# uc3906_New_Version.net
KiCad netlist of a schematic drawn in EAGLE
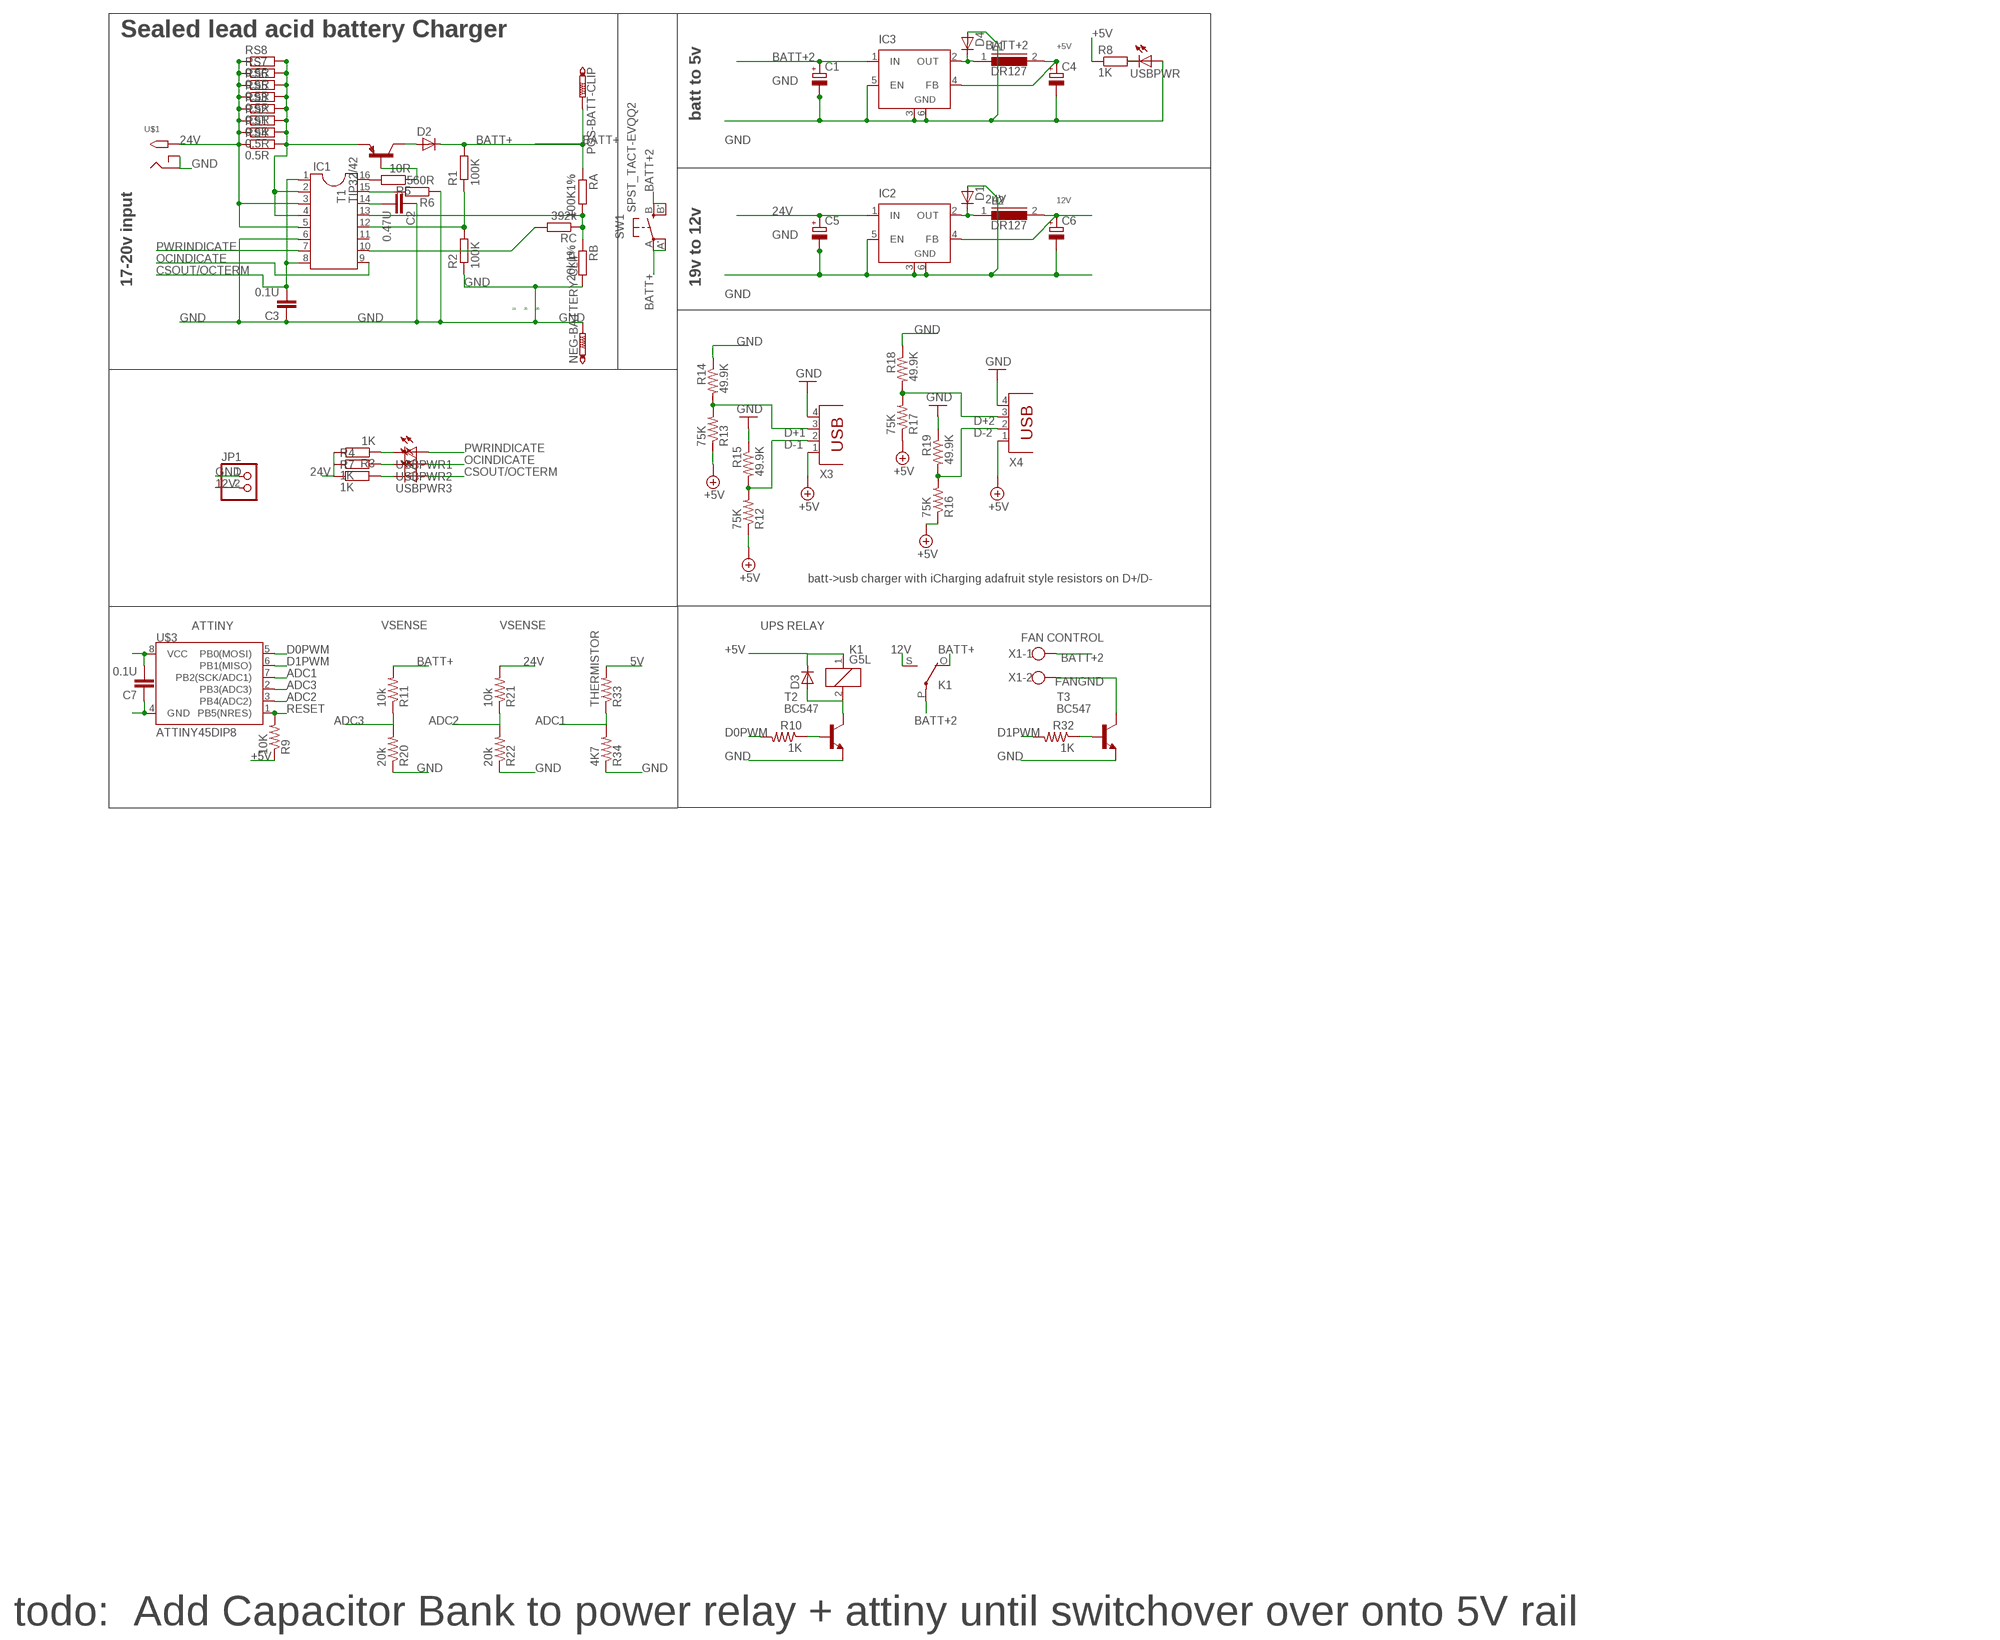
[diagram p0: schematic, sheet 1]

(export (version "E")
  (design (tool "Eeschema 10.0.6"))
  (components
    (comp (ref "C1")
      (value "CPOL-EUE")
      (footprint "eagle-import:PANASONIC_E")
      (libsource (lib "eagle-import") (part "CPOL-EUE"))
    )
    (comp (ref "C2")
      (value "0.47U")
      (footprint "eagle-import:C1206")
      (libsource (lib "eagle-import") (part "C-EUC1206"))
    )
    (comp (ref "C3")
      (value "0.1U")
      (footprint "eagle-import:C1206")
      (libsource (lib "eagle-import") (part "C-EUC1206"))
    )
    (comp (ref "C4")
      (value "CPOL-EUE")
      (footprint "eagle-import:PANASONIC_E")
      (libsource (lib "eagle-import") (part "CPOL-EUE"))
    )
    (comp (ref "C5")
      (value "CPOL-EUE")
      (footprint "eagle-import:PANASONIC_E")
      (libsource (lib "eagle-import") (part "CPOL-EUE"))
    )
    (comp (ref "C6")
      (value "CPOL-EUE")
      (footprint "eagle-import:PANASONIC_E")
      (libsource (lib "eagle-import") (part "CPOL-EUE"))
    )
    (comp (ref "C7")
      (value "0.1U")
      (footprint "eagle-import:C1206")
      (libsource (lib "eagle-import") (part "C-EUC1206"))
    )
    (comp (ref "D1")
      (value "D-SOD-87")
      (footprint "eagle-import:SOD87")
      (libsource (lib "eagle-import") (part "D-SOD-87"))
    )
    (comp (ref "D2")
      (value "D-MLL-41")
      (footprint "eagle-import:MELF-MLL41")
      (libsource (lib "eagle-import") (part "D-MLL-41"))
    )
    (comp (ref "D3")
      (value "D-MLL-41")
      (footprint "eagle-import:MELF-MLL41")
      (libsource (lib "eagle-import") (part "D-MLL-41"))
    )
    (comp (ref "D4")
      (value "D-SOD-87")
      (footprint "eagle-import:SOD87")
      (libsource (lib "eagle-import") (part "D-SOD-87"))
    )
    (comp (ref "IC1")
      (value "DIL16")
      (footprint "eagle-import:DIL16")
      (libsource (lib "eagle-import") (part "DIL16"))
    )
    (comp (ref "IC2")
      (value "LM2596S")
      (footprint "eagle-import:TO263-5")
      (libsource (lib "eagle-import") (part "LM2596S"))
    )
    (comp (ref "IC3")
      (value "LM2596S")
      (footprint "eagle-import:TO263-5")
      (libsource (lib "eagle-import") (part "LM2596S"))
    )
    (comp (ref "JP1")
      (value "PINHD-1X2")
      (footprint "eagle-import:1X02")
      (libsource (lib "eagle-import") (part "PINHD-1X2"))
    )
    (comp (ref "K1")
      (value "G5L")
      (footprint "eagle-import:G5LE")
      (libsource (lib "eagle-import") (part "G5L"))
    )
    (comp (ref "L1")
      (value "DR127")
      (footprint "eagle-import:DR127")
      (libsource (lib "eagle-import") (part "DR127"))
    )
    (comp (ref "L2")
      (value "DR127")
      (footprint "eagle-import:DR127")
      (libsource (lib "eagle-import") (part "DR127"))
    )
    (comp (ref "NEG-BATTERY-CLIP")
      (value "PTR1PAD1-20Y")
      (footprint "eagle-import:P1-20Y")
      (libsource (lib "eagle-import") (part "PTR1PAD1-20Y"))
    )
    (comp (ref "POS-BATT-CLIP")
      (value "PTR1PAD1-20Y")
      (footprint "eagle-import:P1-20Y")
      (libsource (lib "eagle-import") (part "PTR1PAD1-20Y"))
    )
    (comp (ref "R1")
      (value "100K")
      (footprint "eagle-import:M1206")
      (libsource (lib "eagle-import") (part "R-EU_M1206"))
    )
    (comp (ref "R2")
      (value "100K")
      (footprint "eagle-import:M1206")
      (libsource (lib "eagle-import") (part "R-EU_M1206"))
    )
    (comp (ref "R3")
      (value "1K")
      (footprint "eagle-import:M1206")
      (libsource (lib "eagle-import") (part "R-EU_M1206"))
    )
    (comp (ref "R4")
      (value "1K")
      (footprint "eagle-import:M1206")
      (libsource (lib "eagle-import") (part "R-EU_M1206"))
    )
    (comp (ref "R5")
      (value "10R")
      (footprint "eagle-import:M1206")
      (libsource (lib "eagle-import") (part "R-EU_M1206"))
    )
    (comp (ref "R6")
      (value "560R")
      (footprint "eagle-import:M1206")
      (libsource (lib "eagle-import") (part "R-EU_M1206"))
    )
    (comp (ref "R7")
      (value "1K")
      (footprint "eagle-import:M1206")
      (libsource (lib "eagle-import") (part "R-EU_M1206"))
    )
    (comp (ref "R8")
      (value "1K")
      (footprint "eagle-import:M1206")
      (libsource (lib "eagle-import") (part "R-EU_M1206"))
    )
    (comp (ref "R9")
      (value "10K")
      (footprint "eagle-import:M1206")
      (libsource (lib "eagle-import") (part "R-US_M1206"))
    )
    (comp (ref "R10")
      (value "1K")
      (footprint "eagle-import:M1206")
      (libsource (lib "eagle-import") (part "R-US_M1206"))
    )
    (comp (ref "R11")
      (value "10k")
      (footprint "eagle-import:M1206")
      (libsource (lib "eagle-import") (part "R-US_M1206"))
    )
    (comp (ref "R12")
      (value "75K")
      (footprint "eagle-import:M1206")
      (libsource (lib "eagle-import") (part "R-US_M1206"))
    )
    (comp (ref "R13")
      (value "75K")
      (footprint "eagle-import:M1206")
      (libsource (lib "eagle-import") (part "R-US_M1206"))
    )
    (comp (ref "R14")
      (value "49.9K")
      (footprint "eagle-import:M1206")
      (libsource (lib "eagle-import") (part "R-US_M1206"))
    )
    (comp (ref "R15")
      (value "49.9K")
      (footprint "eagle-import:M1206")
      (libsource (lib "eagle-import") (part "R-US_M1206"))
    )
    (comp (ref "R16")
      (value "75K")
      (footprint "eagle-import:M1206")
      (libsource (lib "eagle-import") (part "R-US_M1206"))
    )
    (comp (ref "R17")
      (value "75K")
      (footprint "eagle-import:M1206")
      (libsource (lib "eagle-import") (part "R-US_M1206"))
    )
    (comp (ref "R18")
      (value "49.9K")
      (footprint "eagle-import:M1206")
      (libsource (lib "eagle-import") (part "R-US_M1206"))
    )
    (comp (ref "R19")
      (value "49.9K")
      (footprint "eagle-import:M1206")
      (libsource (lib "eagle-import") (part "R-US_M1206"))
    )
    (comp (ref "R20")
      (value "20k")
      (footprint "eagle-import:M1206")
      (libsource (lib "eagle-import") (part "R-US_M1206"))
    )
    (comp (ref "R21")
      (value "10k")
      (footprint "eagle-import:M1206")
      (libsource (lib "eagle-import") (part "R-US_M1206"))
    )
    (comp (ref "R22")
      (value "20k")
      (footprint "eagle-import:M1206")
      (libsource (lib "eagle-import") (part "R-US_M1206"))
    )
    (comp (ref "R32")
      (value "1K")
      (footprint "eagle-import:M1206")
      (libsource (lib "eagle-import") (part "R-US_M1206"))
    )
    (comp (ref "R33")
      (value "THERMISTOR")
      (footprint "eagle-import:M1206")
      (libsource (lib "eagle-import") (part "R-US_M1206"))
    )
    (comp (ref "R34")
      (value "4K7")
      (footprint "eagle-import:M1206")
      (libsource (lib "eagle-import") (part "R-US_M1206"))
    )
    (comp (ref "RA")
      (value "100K1%")
      (footprint "eagle-import:M1206")
      (libsource (lib "eagle-import") (part "R-EU_M1206"))
    )
    (comp (ref "RB")
      (value "20k1%")
      (footprint "eagle-import:M1206")
      (libsource (lib "eagle-import") (part "R-EU_M1206"))
    )
    (comp (ref "RC")
      (value "392k")
      (footprint "eagle-import:M1206")
      (libsource (lib "eagle-import") (part "R-EU_M1206"))
    )
    (comp (ref "RS1")
      (value "0.5R")
      (footprint "eagle-import:R2512")
      (libsource (lib "eagle-import") (part "resistor_348_R-EU_R2512"))
    )
    (comp (ref "RS2")
      (value "0.5R")
      (footprint "eagle-import:R2512")
      (libsource (lib "eagle-import") (part "resistor_348_R-EU_R2512"))
    )
    (comp (ref "RS3")
      (value "0.5R")
      (footprint "eagle-import:R2512")
      (libsource (lib "eagle-import") (part "resistor_348_R-EU_R2512"))
    )
    (comp (ref "RS4")
      (value "0.5R")
      (footprint "eagle-import:R2512")
      (libsource (lib "eagle-import") (part "resistor_348_R-EU_R2512"))
    )
    (comp (ref "RS5")
      (value "0.5R")
      (footprint "eagle-import:R2512")
      (libsource (lib "eagle-import") (part "resistor_348_R-EU_R2512"))
    )
    (comp (ref "RS6")
      (value "0.5R")
      (footprint "eagle-import:R2512")
      (libsource (lib "eagle-import") (part "resistor_348_R-EU_R2512"))
    )
    (comp (ref "RS7")
      (value "0.5R")
      (footprint "eagle-import:R2512")
      (libsource (lib "eagle-import") (part "resistor_348_R-EU_R2512"))
    )
    (comp (ref "RS8")
      (value "0.5R")
      (footprint "eagle-import:R2512")
      (libsource (lib "eagle-import") (part "resistor_348_R-EU_R2512"))
    )
    (comp (ref "SW1")
      (value "SPST_TACT-EVQQ2")
      (footprint "eagle-import:EVQ-Q2")
      (libsource (lib "eagle-import") (part "SPST_TACT-EVQQ2"))
    )
    (comp (ref "T1")
      (value "TIP32/42")
      (footprint "eagle-import:TO220")
      (libsource (lib "eagle-import") (part "TIP32C"))
    )
    (comp (ref "T2")
      (value "BC547")
      (footprint "eagle-import:TO92")
      (libsource (lib "eagle-import") (part "BC547"))
    )
    (comp (ref "T3")
      (value "BC547")
      (footprint "eagle-import:TO92")
      (libsource (lib "eagle-import") (part "BC547"))
    )
    (comp (ref "U$1")
      (value "2.1MMJACKTHM")
      (footprint "eagle-import:PJ-102A")
      (libsource (lib "eagle-import") (part "2.1MMJACKTHM"))
    )
    (comp (ref "U$3")
      (value "ATTINY45DIP8")
      (footprint "eagle-import:DIP08")
      (libsource (lib "eagle-import") (part "ATTINY45DIP8"))
    )
    (comp (ref "USBPWR")
      (value "LED3MM")
      (footprint "eagle-import:LED3MM")
      (libsource (lib "eagle-import") (part "LED3MM"))
    )
    (comp (ref "USBPWR1")
      (value "LEDCHIPLED_1206")
      (footprint "eagle-import:CHIPLED_1206")
      (libsource (lib "eagle-import") (part "LEDCHIPLED_1206"))
    )
    (comp (ref "USBPWR2")
      (value "LEDCHIPLED_1206")
      (footprint "eagle-import:CHIPLED_1206")
      (libsource (lib "eagle-import") (part "LEDCHIPLED_1206"))
    )
    (comp (ref "USBPWR3")
      (value "LEDCHIPLED_1206")
      (footprint "eagle-import:CHIPLED_1206")
      (libsource (lib "eagle-import") (part "LEDCHIPLED_1206"))
    )
    (comp (ref "X1")
      (value "W237-102")
      (footprint "eagle-import:W237-102")
      (fields (field (name "MPN") "237-102"))
      (libsource (lib "eagle-import") (part "W237-102"))
    )
    (comp (ref "X3")
      (value "PN87520")
      (footprint "eagle-import:PN87520")
      (libsource (lib "eagle-import") (part "PN87520"))
    )
    (comp (ref "X4")
      (value "PN87520")
      (footprint "eagle-import:PN87520")
      (libsource (lib "eagle-import") (part "PN87520"))
    )
  )
  (nets
    (net (code "1") (name "+5V") (class "Default")
      (node (ref "C4") (pin "+") (pinfunction "+_+") (pintype "passive"))
      (node (ref "C7") (pin "2") (pinfunction "2_2") (pintype "passive"))
      (node (ref "D3") (pin "1") (pinfunction "C_1") (pintype "passive"))
      (node (ref "IC3") (pin "4") (pinfunction "FB_4") (pintype "input"))
      (node (ref "K1") (pin "1") (pinfunction "1_1") (pintype "passive"))
      (node (ref "L1") (pin "2") (pinfunction "2_2") (pintype "passive"))
      (node (ref "R12") (pin "1") (pinfunction "1_1") (pintype "passive"))
      (node (ref "R13") (pin "1") (pinfunction "1_1") (pintype "passive"))
      (node (ref "R16") (pin "1") (pinfunction "1_1") (pintype "passive"))
      (node (ref "R17") (pin "1") (pinfunction "1_1") (pintype "passive"))
      (node (ref "R8") (pin "1") (pinfunction "1_1") (pintype "passive"))
      (node (ref "R9") (pin "1") (pinfunction "1_1") (pintype "passive"))
      (node (ref "U$3") (pin "8") (pinfunction "VCC_8") (pintype "bidirectional"))
      (node (ref "X3") (pin "1") (pinfunction "1_1") (pintype "passive"))
      (node (ref "X4") (pin "1") (pinfunction "1_1") (pintype "passive"))
    )
    (net (code "2") (name "/5V") (class "Default")
      (node (ref "R33") (pin "2") (pinfunction "2_2") (pintype "passive"))
    )
    (net (code "3") (name "/12V") (class "Default")
      (node (ref "C6") (pin "+") (pinfunction "+_+") (pintype "passive"))
      (node (ref "IC2") (pin "4") (pinfunction "FB_4") (pintype "input"))
      (node (ref "JP1") (pin "2") (pinfunction "2_2") (pintype "passive"))
      (node (ref "K1") (pin "S") (pinfunction "S_S") (pintype "passive"))
      (node (ref "L2") (pin "2") (pinfunction "2_2") (pintype "passive"))
    )
    (net (code "4") (name "/24V") (class "Default")
      (node (ref "C5") (pin "+") (pinfunction "+_+") (pintype "passive"))
      (node (ref "IC1") (pin "3") (pinfunction "3_3") (pintype "passive"))
      (node (ref "IC1") (pin "5") (pinfunction "5_5") (pintype "passive"))
      (node (ref "IC2") (pin "1") (pinfunction "IN_1") (pintype "input"))
      (node (ref "R21") (pin "2") (pinfunction "2_2") (pintype "passive"))
      (node (ref "R3") (pin "2") (pinfunction "2_2") (pintype "passive"))
      (node (ref "R4") (pin "1") (pinfunction "1_1") (pintype "passive"))
      (node (ref "R7") (pin "1") (pinfunction "1_1") (pintype "passive"))
      (node (ref "RS1") (pin "1") (pinfunction "1_1") (pintype "passive"))
      (node (ref "RS2") (pin "1") (pinfunction "1_1") (pintype "passive"))
      (node (ref "RS3") (pin "1") (pinfunction "1_1") (pintype "passive"))
      (node (ref "RS4") (pin "1") (pinfunction "1_1") (pintype "passive"))
      (node (ref "RS5") (pin "1") (pinfunction "1_1") (pintype "passive"))
      (node (ref "RS6") (pin "1") (pinfunction "1_1") (pintype "passive"))
      (node (ref "RS7") (pin "1") (pinfunction "1_1") (pintype "passive"))
      (node (ref "RS8") (pin "1") (pinfunction "1_1") (pintype "passive"))
      (node (ref "U$1") (pin "TIP") (pinfunction "TIP_TIP") (pintype "bidirectional"))
    )
    (net (code "5") (name "/ADC1") (class "Default")
      (node (ref "R33") (pin "1") (pinfunction "1_1") (pintype "passive"))
      (node (ref "R34") (pin "2") (pinfunction "2_2") (pintype "passive"))
      (node (ref "U$3") (pin "7") (pinfunction "PB2(SCK/ADC1)_7") (pintype "bidirectional"))
    )
    (net (code "6") (name "/ADC2") (class "Default")
      (node (ref "R21") (pin "1") (pinfunction "1_1") (pintype "passive"))
      (node (ref "R22") (pin "2") (pinfunction "2_2") (pintype "passive"))
      (node (ref "U$3") (pin "3") (pinfunction "PB4(ADC2)_3") (pintype "bidirectional"))
    )
    (net (code "7") (name "/ADC3") (class "Default")
      (node (ref "R11") (pin "1") (pinfunction "1_1") (pintype "passive"))
      (node (ref "R20") (pin "2") (pinfunction "2_2") (pintype "passive"))
      (node (ref "U$3") (pin "2") (pinfunction "PB3(ADC3)_2") (pintype "bidirectional"))
    )
    (net (code "8") (name "/BATT+") (class "Default")
      (node (ref "D2") (pin "1") (pinfunction "C_1") (pintype "passive"))
      (node (ref "K1") (pin "O") (pinfunction "O_O") (pintype "passive"))
      (node (ref "POS-BATT-CLIP") (pin "TP") (pinfunction "TP_TP") (pintype "input"))
      (node (ref "R1") (pin "2") (pinfunction "2_2") (pintype "passive"))
      (node (ref "R11") (pin "2") (pinfunction "2_2") (pintype "passive"))
      (node (ref "RA") (pin "1") (pinfunction "1_1") (pintype "passive"))
      (node (ref "SW1") (pin "A") (pinfunction "P_A") (pintype "passive"))
      (node (ref "SW1") (pin "A'") (pinfunction "P1_A'") (pintype "passive"))
    )
    (net (code "9") (name "/BATT+2") (class "Default")
      (node (ref "C1") (pin "+") (pinfunction "+_+") (pintype "passive"))
      (node (ref "IC3") (pin "1") (pinfunction "IN_1") (pintype "input"))
      (node (ref "K1") (pin "P") (pinfunction "P_P") (pintype "passive"))
      (node (ref "SW1") (pin "B") (pinfunction "S_B") (pintype "passive"))
      (node (ref "SW1") (pin "B'") (pinfunction "S1_B'") (pintype "passive"))
      (node (ref "X1") (pin "1") (pinfunction "KL_1") (pintype "passive"))
    )
    (net (code "10") (name "/CSOUT{slash}OCTERM") (class "Default")
      (node (ref "C3") (pin "2") (pinfunction "2_2") (pintype "passive"))
      (node (ref "IC1") (pin "1") (pinfunction "1_1") (pintype "passive"))
      (node (ref "IC1") (pin "8") (pinfunction "8_8") (pintype "passive"))
      (node (ref "USBPWR3") (pin "A") (pinfunction "A_A") (pintype "passive"))
    )
    (net (code "11") (name "/D+1") (class "Default")
      (node (ref "R13") (pin "2") (pinfunction "2_2") (pintype "passive"))
      (node (ref "R14") (pin "2") (pinfunction "2_2") (pintype "passive"))
      (node (ref "X3") (pin "3") (pinfunction "3_3") (pintype "passive"))
    )
    (net (code "12") (name "/D+2") (class "Default")
      (node (ref "R17") (pin "2") (pinfunction "2_2") (pintype "passive"))
      (node (ref "R18") (pin "2") (pinfunction "2_2") (pintype "passive"))
      (node (ref "X4") (pin "3") (pinfunction "3_3") (pintype "passive"))
    )
    (net (code "13") (name "/D-1") (class "Default")
      (node (ref "R12") (pin "2") (pinfunction "2_2") (pintype "passive"))
      (node (ref "R15") (pin "2") (pinfunction "2_2") (pintype "passive"))
      (node (ref "X3") (pin "2") (pinfunction "2_2") (pintype "passive"))
    )
    (net (code "14") (name "/D-2") (class "Default")
      (node (ref "R16") (pin "2") (pinfunction "2_2") (pintype "passive"))
      (node (ref "R19") (pin "2") (pinfunction "2_2") (pintype "passive"))
      (node (ref "X4") (pin "2") (pinfunction "2_2") (pintype "passive"))
    )
    (net (code "15") (name "/D0PWM") (class "Default")
      (node (ref "R10") (pin "2") (pinfunction "2_2") (pintype "passive"))
      (node (ref "U$3") (pin "5") (pinfunction "PB0(MOSI)_5") (pintype "bidirectional"))
    )
    (net (code "16") (name "/D1PWM") (class "Default")
      (node (ref "R32") (pin "2") (pinfunction "2_2") (pintype "passive"))
      (node (ref "U$3") (pin "6") (pinfunction "PB1(MISO)_6") (pintype "bidirectional"))
    )
    (net (code "17") (name "/FANGND") (class "Default")
      (node (ref "T3") (pin "3") (pinfunction "C_3") (pintype "passive"))
      (node (ref "X1") (pin "2") (pinfunction "KL_2") (pintype "passive"))
    )
    (net (code "18") (name "/OCINDICATE") (class "Default")
      (node (ref "IC1") (pin "9") (pinfunction "9_9") (pintype "passive"))
      (node (ref "USBPWR2") (pin "A") (pinfunction "A_A") (pintype "passive"))
    )
    (net (code "19") (name "/PWRINDICATE") (class "Default")
      (node (ref "IC1") (pin "7") (pinfunction "7_7") (pintype "passive"))
      (node (ref "USBPWR1") (pin "A") (pinfunction "A_A") (pintype "passive"))
    )
    (net (code "20") (name "/RESET") (class "Default")
      (node (ref "R9") (pin "2") (pinfunction "2_2") (pintype "passive"))
      (node (ref "U$3") (pin "1") (pinfunction "PB5(NRES)_1") (pintype "bidirectional"))
    )
    (net (code "21") (name "GND") (class "Default")
      (node (ref "C1") (pin "-") (pinfunction "-_-") (pintype "passive"))
      (node (ref "C2") (pin "1") (pinfunction "1_1") (pintype "passive"))
      (node (ref "C3") (pin "1") (pinfunction "1_1") (pintype "passive"))
      (node (ref "C4") (pin "-") (pinfunction "-_-") (pintype "passive"))
      (node (ref "C5") (pin "-") (pinfunction "-_-") (pintype "passive"))
      (node (ref "C6") (pin "-") (pinfunction "-_-") (pintype "passive"))
      (node (ref "C7") (pin "1") (pinfunction "1_1") (pintype "passive"))
      (node (ref "D1") (pin "2") (pinfunction "A_2") (pintype "passive"))
      (node (ref "D4") (pin "2") (pinfunction "A_2") (pintype "passive"))
      (node (ref "IC1") (pin "6") (pinfunction "6_6") (pintype "passive"))
      (node (ref "IC2") (pin "3") (pinfunction "GND_3") (pintype "power_in"))
      (node (ref "IC2") (pin "5") (pinfunction "EN_5") (pintype "input"))
      (node (ref "IC2") (pin "6") (pinfunction "GND_6") (pintype "power_in"))
      (node (ref "IC3") (pin "3") (pinfunction "GND_3") (pintype "power_in"))
      (node (ref "IC3") (pin "5") (pinfunction "EN_5") (pintype "input"))
      (node (ref "IC3") (pin "6") (pinfunction "GND_6") (pintype "power_in"))
      (node (ref "JP1") (pin "1") (pinfunction "1_1") (pintype "passive"))
      (node (ref "NEG-BATTERY-CLIP") (pin "TP") (pinfunction "TP_TP") (pintype "input"))
      (node (ref "R14") (pin "1") (pinfunction "1_1") (pintype "passive"))
      (node (ref "R15") (pin "1") (pinfunction "1_1") (pintype "passive"))
      (node (ref "R18") (pin "1") (pinfunction "1_1") (pintype "passive"))
      (node (ref "R19") (pin "1") (pinfunction "1_1") (pintype "passive"))
      (node (ref "R2") (pin "1") (pinfunction "1_1") (pintype "passive"))
      (node (ref "R20") (pin "1") (pinfunction "1_1") (pintype "passive"))
      (node (ref "R22") (pin "1") (pinfunction "1_1") (pintype "passive"))
      (node (ref "R34") (pin "1") (pinfunction "1_1") (pintype "passive"))
      (node (ref "R6") (pin "1") (pinfunction "1_1") (pintype "passive"))
      (node (ref "RB") (pin "2") (pinfunction "2_2") (pintype "passive"))
      (node (ref "T2") (pin "1") (pinfunction "E_1") (pintype "passive"))
      (node (ref "T3") (pin "1") (pinfunction "E_1") (pintype "passive"))
      (node (ref "U$1") (pin "RING") (pinfunction "RING_RING") (pintype "bidirectional"))
      (node (ref "U$1") (pin "RING_SW") (pinfunction "RING_SW_RING_SW") (pintype "bidirectional"))
      (node (ref "U$3") (pin "4") (pinfunction "GND_4") (pintype "bidirectional"))
      (node (ref "USBPWR") (pin "A") (pinfunction "A_A") (pintype "passive"))
      (node (ref "X3") (pin "4") (pinfunction "4_4") (pintype "passive"))
      (node (ref "X4") (pin "4") (pinfunction "4_4") (pintype "passive"))
    )
    (net (code "22") (name "Net-(C2-Pad2)") (class "Default")
      (node (ref "C2") (pin "2") (pinfunction "2_2") (pintype "passive"))
      (node (ref "IC1") (pin "14") (pinfunction "14_14") (pintype "passive"))
    )
    (net (code "23") (name "Net-(D1-C)") (class "Default")
      (node (ref "D1") (pin "1") (pinfunction "C_1") (pintype "passive"))
      (node (ref "IC2") (pin "2") (pinfunction "OUT_2") (pintype "output"))
      (node (ref "L2") (pin "1") (pinfunction "1_1") (pintype "passive"))
    )
    (net (code "24") (name "Net-(D2-A)") (class "Default")
      (node (ref "D2") (pin "2") (pinfunction "A_2") (pintype "passive"))
      (node (ref "T1") (pin "2") (pinfunction "C_2") (pintype "passive"))
    )
    (net (code "25") (name "Net-(D3-A)") (class "Default")
      (node (ref "D3") (pin "2") (pinfunction "A_2") (pintype "passive"))
      (node (ref "K1") (pin "2") (pinfunction "2_2") (pintype "passive"))
      (node (ref "T2") (pin "3") (pinfunction "C_3") (pintype "passive"))
    )
    (net (code "26") (name "Net-(D4-C)") (class "Default")
      (node (ref "D4") (pin "1") (pinfunction "C_1") (pintype "passive"))
      (node (ref "IC3") (pin "2") (pinfunction "OUT_2") (pintype "output"))
      (node (ref "L1") (pin "1") (pinfunction "1_1") (pintype "passive"))
    )
    (net (code "27") (name "Net-(IC1-Pad10)") (class "Default")
      (node (ref "IC1") (pin "10") (pinfunction "10_10") (pintype "passive"))
      (node (ref "RC") (pin "2") (pinfunction "2_2") (pintype "passive"))
    )
    (net (code "28") (name "Net-(IC1-Pad12)") (class "Default")
      (node (ref "IC1") (pin "12") (pinfunction "12_12") (pintype "passive"))
      (node (ref "R1") (pin "1") (pinfunction "1_1") (pintype "passive"))
      (node (ref "R2") (pin "2") (pinfunction "2_2") (pintype "passive"))
    )
    (net (code "29") (name "Net-(IC1-Pad13)") (class "Default")
      (node (ref "IC1") (pin "13") (pinfunction "13_13") (pintype "passive"))
      (node (ref "RA") (pin "2") (pinfunction "2_2") (pintype "passive"))
      (node (ref "RB") (pin "1") (pinfunction "1_1") (pintype "passive"))
      (node (ref "RC") (pin "1") (pinfunction "1_1") (pintype "passive"))
    )
    (net (code "30") (name "Net-(IC1-Pad15)") (class "Default")
      (node (ref "IC1") (pin "15") (pinfunction "15_15") (pintype "passive"))
      (node (ref "R6") (pin "2") (pinfunction "2_2") (pintype "passive"))
    )
    (net (code "31") (name "Net-(IC1-Pad16)") (class "Default")
      (node (ref "IC1") (pin "16") (pinfunction "16_16") (pintype "passive"))
      (node (ref "R5") (pin "2") (pinfunction "2_2") (pintype "passive"))
    )
    (net (code "32") (name "Net-(R3-Pad1)") (class "Default")
      (node (ref "R3") (pin "1") (pinfunction "1_1") (pintype "passive"))
      (node (ref "USBPWR1") (pin "C") (pinfunction "C_C") (pintype "passive"))
    )
    (net (code "33") (name "Net-(R4-Pad2)") (class "Default")
      (node (ref "R4") (pin "2") (pinfunction "2_2") (pintype "passive"))
      (node (ref "USBPWR2") (pin "C") (pinfunction "C_C") (pintype "passive"))
    )
    (net (code "34") (name "Net-(R7-Pad2)") (class "Default")
      (node (ref "R7") (pin "2") (pinfunction "2_2") (pintype "passive"))
      (node (ref "USBPWR3") (pin "C") (pinfunction "C_C") (pintype "passive"))
    )
    (net (code "35") (name "Net-(T1-B)") (class "Default")
      (node (ref "R5") (pin "1") (pinfunction "1_1") (pintype "passive"))
      (node (ref "T1") (pin "1") (pinfunction "B_1") (pintype "passive"))
    )
    (net (code "36") (name "Net-(T1-E)") (class "Default")
      (node (ref "IC1") (pin "2") (pinfunction "2_2") (pintype "passive"))
      (node (ref "IC1") (pin "4") (pinfunction "4_4") (pintype "passive"))
      (node (ref "RS1") (pin "2") (pinfunction "2_2") (pintype "passive"))
      (node (ref "RS2") (pin "2") (pinfunction "2_2") (pintype "passive"))
      (node (ref "RS3") (pin "2") (pinfunction "2_2") (pintype "passive"))
      (node (ref "RS4") (pin "2") (pinfunction "2_2") (pintype "passive"))
      (node (ref "RS5") (pin "2") (pinfunction "2_2") (pintype "passive"))
      (node (ref "RS6") (pin "2") (pinfunction "2_2") (pintype "passive"))
      (node (ref "RS7") (pin "2") (pinfunction "2_2") (pintype "passive"))
      (node (ref "RS8") (pin "2") (pinfunction "2_2") (pintype "passive"))
      (node (ref "T1") (pin "3") (pinfunction "E_3") (pintype "passive"))
    )
    (net (code "37") (name "Net-(T2-B)") (class "Default")
      (node (ref "R10") (pin "1") (pinfunction "1_1") (pintype "passive"))
      (node (ref "T2") (pin "2") (pinfunction "B_2") (pintype "passive"))
    )
    (net (code "38") (name "Net-(T3-B)") (class "Default")
      (node (ref "R32") (pin "1") (pinfunction "1_1") (pintype "passive"))
      (node (ref "T3") (pin "2") (pinfunction "B_2") (pintype "passive"))
    )
    (net (code "39") (name "Net-(USBPWR-C)") (class "Default")
      (node (ref "R8") (pin "2") (pinfunction "2_2") (pintype "passive"))
      (node (ref "USBPWR") (pin "K") (pinfunction "C_K") (pintype "passive"))
    )
    (net (code "40") (name "unconnected-(IC1-Pad11)") (class "Default")
      (node (ref "IC1") (pin "11") (pinfunction "11_11") (pintype "passive"))
    )
  )
)
